# ETHERNET.net
KiCad netlist of a schematic drawn in Altium Designer
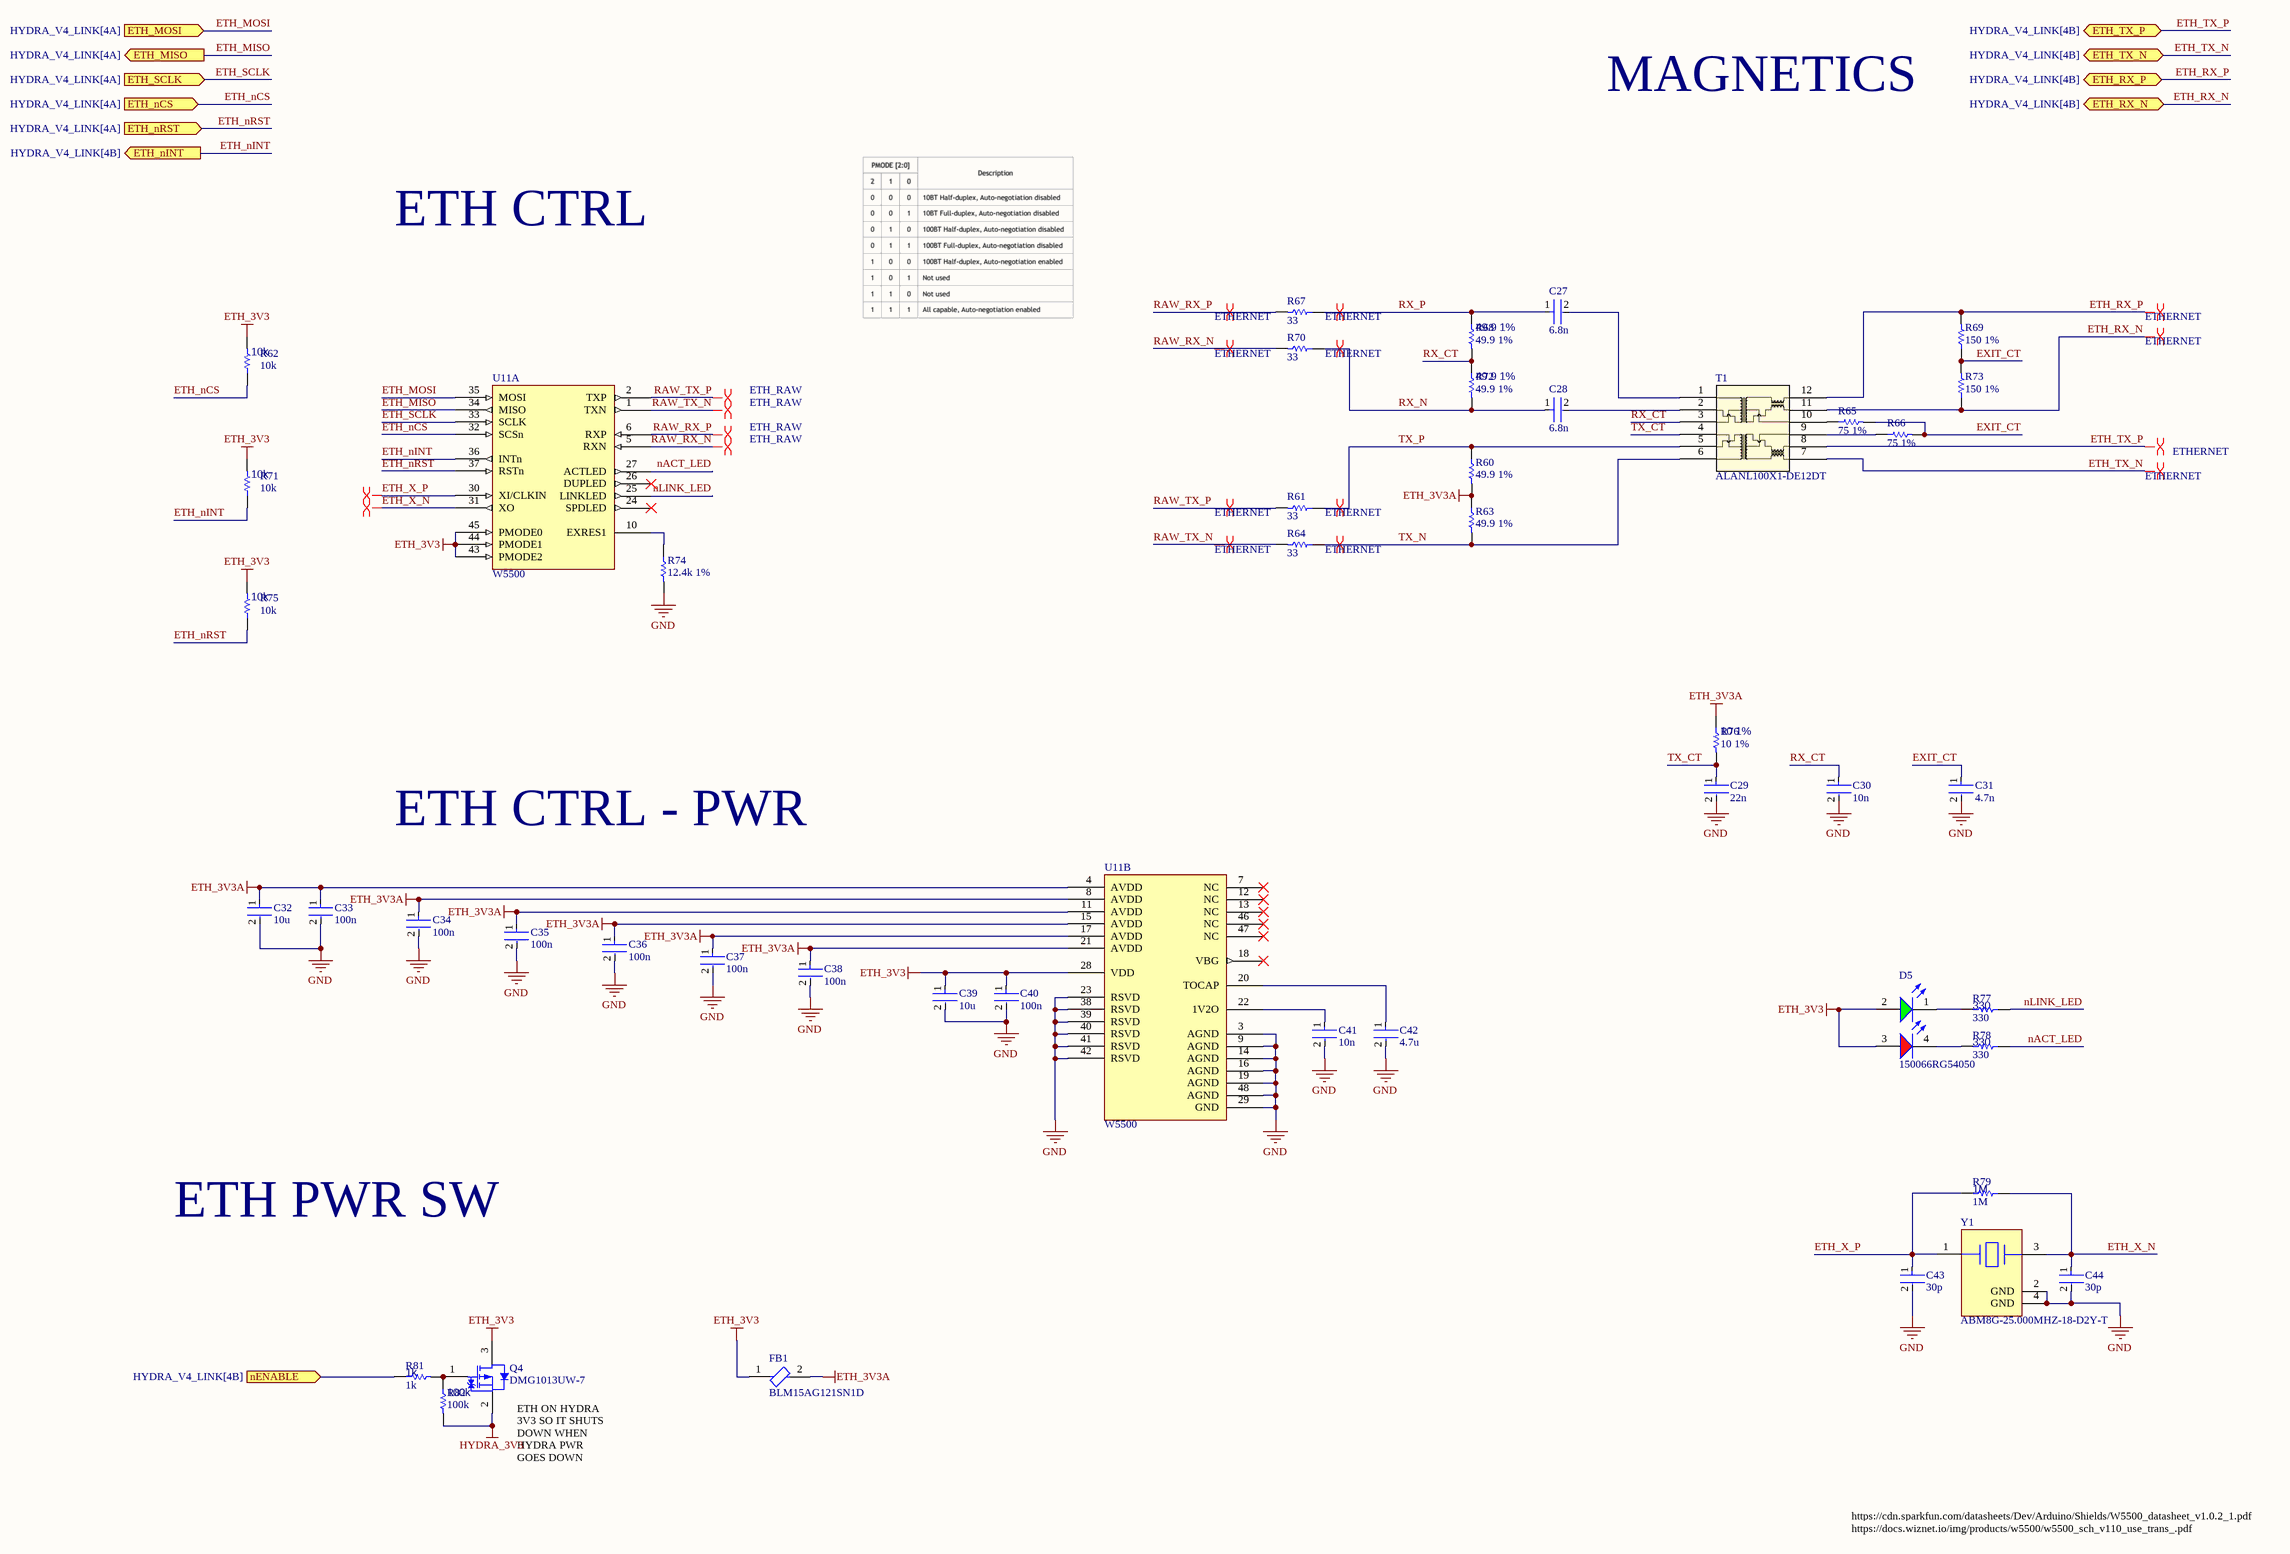
[diagram p0: ETHERNET.SchDoc]

(export (version "E")
  (design (tool "Eeschema 10.0.6"))
  (components
    (comp (ref "C27")
      (value "6.8n")
      (footprint "FP-0402-L_1_0_0_05-W_0_5-IPC_A")
      (description "LARGE PADS, 0402 CAP, CHANGE COMMENT TO MATCH REAL P/N")
      (libsource (lib "Space Concordia") (part "b4654b650e69147ec39a6b967a45e02"))
    )
    (comp (ref "C28")
      (value "6.8n")
      (footprint "FP-0402-L_1_0_0_05-W_0_5-IPC_A")
      (description "LARGE PADS, 0402 CAP, CHANGE COMMENT TO MATCH REAL P/N")
      (libsource (lib "Space Concordia") (part "b4654b650e69147ec39a6b967a45e02"))
    )
    (comp (ref "C29")
      (value "22n")
      (footprint "FP-0402-L_1_0_0_05-W_0_5-IPC_A")
      (description "LARGE PADS, 0402 CAP, CHANGE COMMENT TO MATCH REAL P/N")
      (libsource (lib "Space Concordia") (part "b4654b650e69147ec39a6b967a45e02"))
    )
    (comp (ref "C30")
      (value "10n")
      (footprint "FP-0402-L_1_0_0_05-W_0_5-IPC_A")
      (description "LARGE PADS, 0402 CAP, CHANGE COMMENT TO MATCH REAL P/N")
      (libsource (lib "Space Concordia") (part "b4654b650e69147ec39a6b967a45e02"))
    )
    (comp (ref "C31")
      (value "4.7n")
      (footprint "FP-0402-L_1_0_0_05-W_0_5-IPC_A")
      (description "LARGE PADS, 0402 CAP, CHANGE COMMENT TO MATCH REAL P/N")
      (libsource (lib "Space Concordia") (part "b4654b650e69147ec39a6b967a45e02"))
    )
    (comp (ref "C32")
      (value "10u")
      (footprint "FP-0402-L_1_0_0_05-W_0_5-IPC_A")
      (description "LARGE PADS, 0402 CAP, CHANGE COMMENT TO MATCH REAL P/N")
      (libsource (lib "Space Concordia") (part "b4654b650e69147ec39a6b967a45e02"))
    )
    (comp (ref "C33")
      (value "100n")
      (footprint "FP-0402-L_1_0_0_05-W_0_5-IPC_A")
      (description "LARGE PADS, 0402 CAP, CHANGE COMMENT TO MATCH REAL P/N")
      (libsource (lib "Space Concordia") (part "b4654b650e69147ec39a6b967a45e02"))
    )
    (comp (ref "C34")
      (value "100n")
      (footprint "FP-0402-L_1_0_0_05-W_0_5-IPC_A")
      (description "LARGE PADS, 0402 CAP, CHANGE COMMENT TO MATCH REAL P/N")
      (libsource (lib "Space Concordia") (part "b4654b650e69147ec39a6b967a45e02"))
    )
    (comp (ref "C35")
      (value "100n")
      (footprint "FP-0402-L_1_0_0_05-W_0_5-IPC_A")
      (description "LARGE PADS, 0402 CAP, CHANGE COMMENT TO MATCH REAL P/N")
      (libsource (lib "Space Concordia") (part "b4654b650e69147ec39a6b967a45e02"))
    )
    (comp (ref "C36")
      (value "100n")
      (footprint "FP-0402-L_1_0_0_05-W_0_5-IPC_A")
      (description "LARGE PADS, 0402 CAP, CHANGE COMMENT TO MATCH REAL P/N")
      (libsource (lib "Space Concordia") (part "b4654b650e69147ec39a6b967a45e02"))
    )
    (comp (ref "C37")
      (value "100n")
      (footprint "FP-0402-L_1_0_0_05-W_0_5-IPC_A")
      (description "LARGE PADS, 0402 CAP, CHANGE COMMENT TO MATCH REAL P/N")
      (libsource (lib "Space Concordia") (part "b4654b650e69147ec39a6b967a45e02"))
    )
    (comp (ref "C38")
      (value "100n")
      (footprint "FP-0402-L_1_0_0_05-W_0_5-IPC_A")
      (description "LARGE PADS, 0402 CAP, CHANGE COMMENT TO MATCH REAL P/N")
      (libsource (lib "Space Concordia") (part "b4654b650e69147ec39a6b967a45e02"))
    )
    (comp (ref "C39")
      (value "10u")
      (footprint "FP-0402-L_1_0_0_05-W_0_5-IPC_A")
      (description "LARGE PADS, 0402 CAP, CHANGE COMMENT TO MATCH REAL P/N")
      (libsource (lib "Space Concordia") (part "b4654b650e69147ec39a6b967a45e02"))
    )
    (comp (ref "C40")
      (value "100n")
      (footprint "FP-0402-L_1_0_0_05-W_0_5-IPC_A")
      (description "LARGE PADS, 0402 CAP, CHANGE COMMENT TO MATCH REAL P/N")
      (libsource (lib "Space Concordia") (part "b4654b650e69147ec39a6b967a45e02"))
    )
    (comp (ref "C41")
      (value "10n")
      (footprint "FP-0402-L_1_0_0_05-W_0_5-IPC_A")
      (description "LARGE PADS, 0402 CAP, CHANGE COMMENT TO MATCH REAL P/N")
      (libsource (lib "Space Concordia") (part "b4654b650e69147ec39a6b967a45e02"))
    )
    (comp (ref "C42")
      (value "4.7u")
      (footprint "FP-0402-L_1_0_0_05-W_0_5-IPC_A")
      (description "LARGE PADS, 0402 CAP, CHANGE COMMENT TO MATCH REAL P/N")
      (libsource (lib "Space Concordia") (part "b4654b650e69147ec39a6b967a45e02"))
    )
    (comp (ref "C43")
      (value "30p")
      (footprint "FP-0402-L_1_0_0_05-W_0_5-IPC_A")
      (description "LARGE PADS, 0402 CAP, CHANGE COMMENT TO MATCH REAL P/N")
      (libsource (lib "Space Concordia") (part "b4654b650e69147ec39a6b967a45e02"))
    )
    (comp (ref "C44")
      (value "30p")
      (footprint "FP-0402-L_1_0_0_05-W_0_5-IPC_A")
      (description "LARGE PADS, 0402 CAP, CHANGE COMMENT TO MATCH REAL P/N")
      (libsource (lib "Space Concordia") (part "b4654b650e69147ec39a6b967a45e02"))
    )
    (comp (ref "D5")
      (value "150066RG54050")
      (footprint "WL-SBCD_0606")
      (description "Led, Red/Grn, 180Mcd/230Mcd, 624Nm/525Nm Rohs Compliant: Yes")
      (fields (field (name "SOURCE") "rgled.SchLib"))
      (libsource (lib "Space Concordia") (part "CMP-004-00034-2"))
    )
    (comp (ref "FB1")
      (value "BLM15AG121SN1D")
      (footprint "FP-BLM15-0_05-MFG")
      (description "Chip Ferrite Bead, 0402, 120Ω @ 100MHz, 0.19Ω, 25%, 550mA")
      (fields (field (name "TOLERANCE") "25%"))
      (libsource (lib "Altium Content Vault") (part "5f30dd21d616792df468990f7003faa"))
    )
    (comp (ref "Q4")
      (value "DMG1013UW-7")
      (footprint "DIOD-SOT323-3_V")
      (fields (field (name "MANUFACTURER") "Diodes Inc"))
      (libsource (lib "Altium Content Vault") (part "PEMOS-GSD-3_C"))
    )
    (comp (ref "R60")
      (value "49.9 1%")
      (footprint "R0603B")
      (description "Resistor")
      (libsource (lib "Space Concordia") (part "Resistor"))
    )
    (comp (ref "R61")
      (value "33")
      (footprint "R0603B")
      (description "Resistor")
      (libsource (lib "Space Concordia") (part "Resistor"))
    )
    (comp (ref "R62")
      (value "10k")
      (footprint "R0603B")
      (description "Resistor")
      (fields (field (name "ALTIUM_VALUE") "10k"))
      (libsource (lib "Space Concordia") (part "Resistor"))
    )
    (comp (ref "R63")
      (value "49.9 1%")
      (footprint "R0603B")
      (description "Resistor")
      (libsource (lib "Space Concordia") (part "Resistor"))
    )
    (comp (ref "R64")
      (value "33")
      (footprint "R0603B")
      (description "Resistor")
      (libsource (lib "Space Concordia") (part "Resistor"))
    )
    (comp (ref "R65")
      (value "75 1%")
      (footprint "R0603B")
      (description "Resistor")
      (libsource (lib "Space Concordia") (part "Resistor"))
    )
    (comp (ref "R66")
      (value "75 1%")
      (footprint "R0603B")
      (description "Resistor")
      (libsource (lib "Space Concordia") (part "Resistor"))
    )
    (comp (ref "R67")
      (value "33")
      (footprint "R0603B")
      (description "Resistor")
      (libsource (lib "Space Concordia") (part "Resistor"))
    )
    (comp (ref "R68")
      (value "49.9 1%")
      (footprint "R0603B")
      (description "Resistor")
      (fields (field (name "ALTIUM_VALUE") "49.9 1%"))
      (libsource (lib "Space Concordia") (part "Resistor"))
    )
    (comp (ref "R69")
      (value "150 1%")
      (footprint "R0603B")
      (description "Resistor")
      (libsource (lib "Space Concordia") (part "Resistor"))
    )
    (comp (ref "R70")
      (value "33")
      (footprint "R0603B")
      (description "Resistor")
      (libsource (lib "Space Concordia") (part "Resistor"))
    )
    (comp (ref "R71")
      (value "10k")
      (footprint "R0603B")
      (description "Resistor")
      (fields (field (name "ALTIUM_VALUE") "10k"))
      (libsource (lib "Space Concordia") (part "Resistor"))
    )
    (comp (ref "R72")
      (value "49.9 1%")
      (footprint "R0603B")
      (description "Resistor")
      (fields (field (name "ALTIUM_VALUE") "49.9 1%"))
      (libsource (lib "Space Concordia") (part "Resistor"))
    )
    (comp (ref "R73")
      (value "150 1%")
      (footprint "R0603B")
      (description "Resistor")
      (libsource (lib "Space Concordia") (part "Resistor"))
    )
    (comp (ref "R74")
      (value "12.4k 1%")
      (footprint "R0603B")
      (description "Resistor")
      (libsource (lib "Space Concordia") (part "Resistor"))
    )
    (comp (ref "R75")
      (value "10k")
      (footprint "R0603B")
      (description "Resistor")
      (fields (field (name "ALTIUM_VALUE") "10k"))
      (libsource (lib "Space Concordia") (part "Resistor"))
    )
    (comp (ref "R76")
      (value "10 1%")
      (footprint "R0603B")
      (description "Resistor")
      (fields (field (name "ALTIUM_VALUE") "10 1%"))
      (libsource (lib "Space Concordia") (part "Resistor"))
    )
    (comp (ref "R77")
      (value "330")
      (footprint "R0603B")
      (description "Resistor")
      (fields (field (name "ALTIUM_VALUE") "330"))
      (libsource (lib "Space Concordia") (part "Resistor"))
    )
    (comp (ref "R78")
      (value "330")
      (footprint "R0603B")
      (description "Resistor")
      (fields (field (name "ALTIUM_VALUE") "330"))
      (libsource (lib "Space Concordia") (part "Resistor"))
    )
    (comp (ref "R79")
      (value "1M")
      (footprint "R0603B")
      (description "Resistor")
      (fields (field (name "ALTIUM_VALUE") "1M"))
      (libsource (lib "Space Concordia") (part "Resistor"))
    )
    (comp (ref "R81")
      (value "1k")
      (footprint "R0603B")
      (description "Resistor")
      (fields (field (name "ALTIUM_VALUE") "1k"))
      (libsource (lib "Space Concordia") (part "Resistor"))
    )
    (comp (ref "R82")
      (value "100k")
      (footprint "R0603B")
      (description "Resistor")
      (fields (field (name "ALTIUM_VALUE") "100k"))
      (libsource (lib "Space Concordia") (part "Resistor"))
    )
    (comp (ref "T1")
      (value "ALANL100X1-DE12DT")
      (footprint "ALANL100X1-DE12DT-Footprint-1")
      (description "Datacom Transformer, LAN; 10/100 BASE-TX; ETHERNET Application(s), 1CT:1CT")
      (libsource (lib "Space Concordia") (part "ALANL100X1-DE12DT"))
    )
    (comp (ref "U11")
      (value "W5500")
      (footprint "TSQFP50P900X900X160-48N")
      (description "Ethernet CTLR Single Chip 10Mbps/100Mbps 3.3V 48-Pin LQFP Reel")
      (libsource (lib "Space Concordia") (part "W5500"))
    )
    (comp (ref "Y1")
      (value "ABM8G-25.000MHZ-18-D2Y-T")
      (footprint "FP-ABM8G-MFG")
      (description "Crystal 25MHz ±20ppm (Tol) ±30ppm (Stability) 18pF FUND 60Ω 4-Pin SMD T/R")
      (fields (field (name "TOLERANCE") "20ppm"))
      (libsource (lib "Altium Content Vault") (part "48e526d86b7f2615d98721063c72f49"))
    )
  )
  (nets
    (net (code "1") (name "/ETH_MISO") (class "Default")
      (node (ref "U11") (pin "34") (pinfunction "MISO_34") (pintype "output"))
    )
    (net (code "2") (name "/ETH_MOSI") (class "Default")
      (node (ref "U11") (pin "35") (pinfunction "MOSI_35") (pintype "input"))
    )
    (net (code "3") (name "/ETH_RX_N") (class "Default")
      (node (ref "R73") (pin "1") (pinfunction "1_1") (pintype "passive"))
      (node (ref "T1") (pin "11") (pinfunction "MX1-_11") (pintype "passive"))
    )
    (net (code "4") (name "/ETH_RX_P") (class "Default")
      (node (ref "R69") (pin "2") (pinfunction "2_2") (pintype "passive"))
      (node (ref "T1") (pin "12") (pinfunction "MX1+_12") (pintype "passive"))
    )
    (net (code "5") (name "/ETH_SCLK") (class "Default")
      (node (ref "U11") (pin "33") (pinfunction "SCLK_33") (pintype "input"))
    )
    (net (code "6") (name "/ETH_TX_N") (class "Default")
      (node (ref "T1") (pin "7") (pinfunction "MX2-_7") (pintype "passive"))
    )
    (net (code "7") (name "/ETH_TX_P") (class "Default")
      (node (ref "T1") (pin "8") (pinfunction "MX2+_8") (pintype "passive"))
    )
    (net (code "8") (name "/ETH_X_N") (class "Default")
      (node (ref "C44") (pin "1") (pinfunction "1_1") (pintype "passive"))
      (node (ref "R79") (pin "1") (pinfunction "1_1") (pintype "passive"))
      (node (ref "U11") (pin "31") (pinfunction "XO_31") (pintype "output"))
      (node (ref "Y1") (pin "3") (pinfunction "3_3") (pintype "passive"))
    )
    (net (code "9") (name "/ETH_X_P") (class "Default")
      (node (ref "C43") (pin "1") (pinfunction "1_1") (pintype "passive"))
      (node (ref "R79") (pin "2") (pinfunction "2_2") (pintype "passive"))
      (node (ref "U11") (pin "30") (pinfunction "XI/CLKIN_30") (pintype "input"))
      (node (ref "Y1") (pin "1") (pinfunction "1_1") (pintype "passive"))
    )
    (net (code "10") (name "/ETH_nCS") (class "Default")
      (node (ref "R62") (pin "1") (pinfunction "1_1") (pintype "passive"))
      (node (ref "U11") (pin "32") (pinfunction "SCSn_32") (pintype "input"))
    )
    (net (code "11") (name "/ETH_nINT") (class "Default")
      (node (ref "R71") (pin "1") (pinfunction "1_1") (pintype "passive"))
      (node (ref "U11") (pin "36") (pinfunction "INTn_36") (pintype "output"))
    )
    (net (code "12") (name "/ETH_nRST") (class "Default")
      (node (ref "R75") (pin "1") (pinfunction "1_1") (pintype "passive"))
      (node (ref "U11") (pin "37") (pinfunction "RSTn_37") (pintype "input"))
    )
    (net (code "13") (name "/EXIT_CT") (class "Default")
      (node (ref "C31") (pin "1") (pinfunction "1_1") (pintype "passive"))
      (node (ref "R65") (pin "2") (pinfunction "2_2") (pintype "passive"))
      (node (ref "R66") (pin "2") (pinfunction "2_2") (pintype "passive"))
      (node (ref "R69") (pin "1") (pinfunction "1_1") (pintype "passive"))
      (node (ref "R73") (pin "2") (pinfunction "2_2") (pintype "passive"))
    )
    (net (code "14") (name "/RAW_RX_N") (class "Default")
      (node (ref "R70") (pin "2") (pinfunction "2_2") (pintype "passive"))
      (node (ref "U11") (pin "5") (pinfunction "RXN_5") (pintype "input"))
    )
    (net (code "15") (name "/RAW_RX_P") (class "Default")
      (node (ref "R67") (pin "2") (pinfunction "2_2") (pintype "passive"))
      (node (ref "U11") (pin "6") (pinfunction "RXP_6") (pintype "input"))
    )
    (net (code "16") (name "/RAW_TX_N") (class "Default")
      (node (ref "R64") (pin "2") (pinfunction "2_2") (pintype "passive"))
      (node (ref "U11") (pin "1") (pinfunction "TXN_1") (pintype "output"))
    )
    (net (code "17") (name "/RAW_TX_P") (class "Default")
      (node (ref "R61") (pin "2") (pinfunction "2_2") (pintype "passive"))
      (node (ref "U11") (pin "2") (pinfunction "TXP_2") (pintype "output"))
    )
    (net (code "18") (name "/RX_CT") (class "Default")
      (node (ref "C30") (pin "1") (pinfunction "1_1") (pintype "passive"))
      (node (ref "R68") (pin "2") (pinfunction "2_2") (pintype "passive"))
      (node (ref "R72") (pin "1") (pinfunction "1_1") (pintype "passive"))
      (node (ref "T1") (pin "3") (pinfunction "TCT1_3") (pintype "passive"))
    )
    (net (code "19") (name "/RX_N") (class "Default")
      (node (ref "C28") (pin "1") (pinfunction "1_1") (pintype "passive"))
      (node (ref "R70") (pin "1") (pinfunction "1_1") (pintype "passive"))
      (node (ref "R72") (pin "2") (pinfunction "2_2") (pintype "passive"))
    )
    (net (code "20") (name "/RX_P") (class "Default")
      (node (ref "C27") (pin "1") (pinfunction "1_1") (pintype "passive"))
      (node (ref "R67") (pin "1") (pinfunction "1_1") (pintype "passive"))
      (node (ref "R68") (pin "1") (pinfunction "1_1") (pintype "passive"))
    )
    (net (code "21") (name "/TX_CT") (class "Default")
      (node (ref "C29") (pin "1") (pinfunction "1_1") (pintype "passive"))
      (node (ref "R76") (pin "2") (pinfunction "2_2") (pintype "passive"))
      (node (ref "T1") (pin "4") (pinfunction "TCT2_4") (pintype "passive"))
    )
    (net (code "22") (name "/TX_N") (class "Default")
      (node (ref "R63") (pin "2") (pinfunction "2_2") (pintype "passive"))
      (node (ref "R64") (pin "1") (pinfunction "1_1") (pintype "passive"))
      (node (ref "T1") (pin "6") (pinfunction "TD2-_6") (pintype "passive"))
    )
    (net (code "23") (name "/TX_P") (class "Default")
      (node (ref "R60") (pin "1") (pinfunction "1_1") (pintype "passive"))
      (node (ref "R61") (pin "1") (pinfunction "1_1") (pintype "passive"))
      (node (ref "T1") (pin "5") (pinfunction "TD2+_5") (pintype "passive"))
    )
    (net (code "24") (name "/nACT_LED") (class "Default")
      (node (ref "R78") (pin "1") (pinfunction "1_1") (pintype "passive"))
      (node (ref "U11") (pin "27") (pinfunction "ACTLED_27") (pintype "output"))
    )
    (net (code "25") (name "/nENABLE") (class "Default")
      (node (ref "R81") (pin "1") (pinfunction "1_1") (pintype "passive"))
    )
    (net (code "26") (name "/nLINK_LED") (class "Default")
      (node (ref "R77") (pin "1") (pinfunction "1_1") (pintype "passive"))
      (node (ref "U11") (pin "25") (pinfunction "LINKLED_25") (pintype "output"))
    )
    (net (code "27") (name "ETH_3V3") (class "Default")
      (node (ref "C39") (pin "1") (pinfunction "1_1") (pintype "passive"))
      (node (ref "C40") (pin "1") (pinfunction "1_1") (pintype "passive"))
      (node (ref "D5") (pin "2") (pinfunction "A_2") (pintype "passive"))
      (node (ref "D5") (pin "3") (pinfunction "A_3") (pintype "passive"))
      (node (ref "FB1") (pin "1") (pinfunction "1_1") (pintype "passive"))
      (node (ref "Q4") (pin "3") (pinfunction "D_3") (pintype "passive"))
      (node (ref "R62") (pin "2") (pinfunction "2_2") (pintype "passive"))
      (node (ref "R71") (pin "2") (pinfunction "2_2") (pintype "passive"))
      (node (ref "R75") (pin "2") (pinfunction "2_2") (pintype "passive"))
      (node (ref "U11") (pin "28") (pinfunction "VDD_28") (pintype "power_in"))
      (node (ref "U11") (pin "43") (pinfunction "PMODE2_43") (pintype "input"))
      (node (ref "U11") (pin "44") (pinfunction "PMODE1_44") (pintype "input"))
      (node (ref "U11") (pin "45") (pinfunction "PMODE0_45") (pintype "input"))
    )
    (net (code "28") (name "ETH_3V3A") (class "Default")
      (node (ref "C32") (pin "1") (pinfunction "1_1") (pintype "passive"))
      (node (ref "C33") (pin "1") (pinfunction "1_1") (pintype "passive"))
      (node (ref "C34") (pin "1") (pinfunction "1_1") (pintype "passive"))
      (node (ref "C35") (pin "1") (pinfunction "1_1") (pintype "passive"))
      (node (ref "C36") (pin "1") (pinfunction "1_1") (pintype "passive"))
      (node (ref "C37") (pin "1") (pinfunction "1_1") (pintype "passive"))
      (node (ref "C38") (pin "1") (pinfunction "1_1") (pintype "passive"))
      (node (ref "FB1") (pin "2") (pinfunction "2_2") (pintype "passive"))
      (node (ref "R60") (pin "2") (pinfunction "2_2") (pintype "passive"))
      (node (ref "R63") (pin "1") (pinfunction "1_1") (pintype "passive"))
      (node (ref "R76") (pin "1") (pinfunction "1_1") (pintype "passive"))
      (node (ref "U11") (pin "11") (pinfunction "AVDD_11") (pintype "power_in"))
      (node (ref "U11") (pin "15") (pinfunction "AVDD_15") (pintype "power_in"))
      (node (ref "U11") (pin "17") (pinfunction "AVDD_17") (pintype "power_in"))
      (node (ref "U11") (pin "21") (pinfunction "AVDD_21") (pintype "power_in"))
      (node (ref "U11") (pin "4") (pinfunction "AVDD_4") (pintype "power_in"))
      (node (ref "U11") (pin "8") (pinfunction "AVDD_8") (pintype "power_in"))
    )
    (net (code "29") (name "GND") (class "Default")
      (node (ref "C29") (pin "2") (pinfunction "2_2") (pintype "passive"))
      (node (ref "C30") (pin "2") (pinfunction "2_2") (pintype "passive"))
      (node (ref "C31") (pin "2") (pinfunction "2_2") (pintype "passive"))
      (node (ref "C32") (pin "2") (pinfunction "2_2") (pintype "passive"))
      (node (ref "C33") (pin "2") (pinfunction "2_2") (pintype "passive"))
      (node (ref "C34") (pin "2") (pinfunction "2_2") (pintype "passive"))
      (node (ref "C35") (pin "2") (pinfunction "2_2") (pintype "passive"))
      (node (ref "C36") (pin "2") (pinfunction "2_2") (pintype "passive"))
      (node (ref "C37") (pin "2") (pinfunction "2_2") (pintype "passive"))
      (node (ref "C38") (pin "2") (pinfunction "2_2") (pintype "passive"))
      (node (ref "C39") (pin "2") (pinfunction "2_2") (pintype "passive"))
      (node (ref "C40") (pin "2") (pinfunction "2_2") (pintype "passive"))
      (node (ref "C41") (pin "2") (pinfunction "2_2") (pintype "passive"))
      (node (ref "C42") (pin "2") (pinfunction "2_2") (pintype "passive"))
      (node (ref "C43") (pin "2") (pinfunction "2_2") (pintype "passive"))
      (node (ref "C44") (pin "2") (pinfunction "2_2") (pintype "passive"))
      (node (ref "R74") (pin "2") (pinfunction "2_2") (pintype "passive"))
      (node (ref "U11") (pin "14") (pinfunction "AGND_14") (pintype "power_in"))
      (node (ref "U11") (pin "16") (pinfunction "AGND_16") (pintype "power_in"))
      (node (ref "U11") (pin "19") (pinfunction "AGND_19") (pintype "power_in"))
      (node (ref "U11") (pin "23") (pinfunction "RSVD_23") (pintype "passive"))
      (node (ref "U11") (pin "29") (pinfunction "GND_29") (pintype "power_in"))
      (node (ref "U11") (pin "3") (pinfunction "AGND_3") (pintype "power_in"))
      (node (ref "U11") (pin "38") (pinfunction "RSVD_38") (pintype "passive"))
      (node (ref "U11") (pin "39") (pinfunction "RSVD_39") (pintype "passive"))
      (node (ref "U11") (pin "40") (pinfunction "RSVD_40") (pintype "passive"))
      (node (ref "U11") (pin "41") (pinfunction "RSVD_41") (pintype "passive"))
      (node (ref "U11") (pin "42") (pinfunction "RSVD_42") (pintype "passive"))
      (node (ref "U11") (pin "48") (pinfunction "AGND_48") (pintype "power_in"))
      (node (ref "U11") (pin "9") (pinfunction "AGND_9") (pintype "power_in"))
      (node (ref "Y1") (pin "2") (pinfunction "GND_2") (pintype "power_in"))
      (node (ref "Y1") (pin "4") (pinfunction "GND_4") (pintype "power_in"))
    )
    (net (code "30") (name "HYDRA_3V3") (class "Default")
      (node (ref "Q4") (pin "2") (pinfunction "S_2") (pintype "passive"))
      (node (ref "R82") (pin "2") (pinfunction "2_2") (pintype "passive"))
    )
    (net (code "31") (name "Net-(D5-K-Pad1)") (class "Default")
      (node (ref "D5") (pin "1") (pinfunction "K_1") (pintype "passive"))
      (node (ref "R77") (pin "2") (pinfunction "2_2") (pintype "passive"))
    )
    (net (code "32") (name "Net-(D5-K-Pad4)") (class "Default")
      (node (ref "D5") (pin "4") (pinfunction "K_4") (pintype "passive"))
      (node (ref "R78") (pin "2") (pinfunction "2_2") (pintype "passive"))
    )
    (net (code "33") (name "Net-(Q4-G)") (class "Default")
      (node (ref "Q4") (pin "1") (pinfunction "G_1") (pintype "passive"))
      (node (ref "R81") (pin "2") (pinfunction "2_2") (pintype "passive"))
      (node (ref "R82") (pin "1") (pinfunction "1_1") (pintype "passive"))
    )
    (net (code "34") (name "Net-(T1-MCT1)") (class "Default")
      (node (ref "R65") (pin "1") (pinfunction "1_1") (pintype "passive"))
      (node (ref "T1") (pin "10") (pinfunction "MCT1_10") (pintype "passive"))
    )
    (net (code "35") (name "Net-(T1-MCT2)") (class "Default")
      (node (ref "R66") (pin "1") (pinfunction "1_1") (pintype "passive"))
      (node (ref "T1") (pin "9") (pinfunction "MCT2_9") (pintype "passive"))
    )
    (net (code "36") (name "Net-(T1-TD1+)") (class "Default")
      (node (ref "C27") (pin "2") (pinfunction "2_2") (pintype "passive"))
      (node (ref "T1") (pin "1") (pinfunction "TD1+_1") (pintype "passive"))
    )
    (net (code "37") (name "Net-(T1-TD1-)") (class "Default")
      (node (ref "C28") (pin "2") (pinfunction "2_2") (pintype "passive"))
      (node (ref "T1") (pin "2") (pinfunction "TD1-_2") (pintype "passive"))
    )
    (net (code "38") (name "Net-(U11A-EXRES1)") (class "Default")
      (node (ref "R74") (pin "1") (pinfunction "1_1") (pintype "passive"))
      (node (ref "U11") (pin "10") (pinfunction "EXRES1_10") (pintype "passive"))
    )
    (net (code "39") (name "Net-(U11B-1V2O)") (class "Default")
      (node (ref "C41") (pin "1") (pinfunction "1_1") (pintype "passive"))
      (node (ref "U11") (pin "22") (pinfunction "1V2O_22") (pintype "power_in"))
    )
    (net (code "40") (name "Net-(U11B-TOCAP)") (class "Default")
      (node (ref "C42") (pin "1") (pinfunction "1_1") (pintype "passive"))
      (node (ref "U11") (pin "20") (pinfunction "TOCAP_20") (pintype "passive"))
    )
    (net (code "41") (name "unconnected-(U11A-DUPLED-Pad26)") (class "Default")
      (node (ref "U11") (pin "26") (pinfunction "DUPLED_26") (pintype "output+no_connect"))
    )
    (net (code "42") (name "unconnected-(U11A-SPDLED-Pad24)") (class "Default")
      (node (ref "U11") (pin "24") (pinfunction "SPDLED_24") (pintype "output+no_connect"))
    )
    (net (code "43") (name "unconnected-(U11B-NC-Pad7)") (class "Default")
      (node (ref "U11") (pin "7") (pinfunction "NC_7") (pintype "passive+no_connect"))
    )
    (net (code "44") (name "unconnected-(U11B-NC-Pad12)") (class "Default")
      (node (ref "U11") (pin "12") (pinfunction "NC_12") (pintype "passive+no_connect"))
    )
    (net (code "45") (name "unconnected-(U11B-NC-Pad13)") (class "Default")
      (node (ref "U11") (pin "13") (pinfunction "NC_13") (pintype "passive+no_connect"))
    )
    (net (code "46") (name "unconnected-(U11B-NC-Pad46)") (class "Default")
      (node (ref "U11") (pin "46") (pinfunction "NC_46") (pintype "passive+no_connect"))
    )
    (net (code "47") (name "unconnected-(U11B-NC-Pad47)") (class "Default")
      (node (ref "U11") (pin "47") (pinfunction "NC_47") (pintype "passive+no_connect"))
    )
    (net (code "48") (name "unconnected-(U11B-VBG-Pad18)") (class "Default")
      (node (ref "U11") (pin "18") (pinfunction "VBG_18") (pintype "output+no_connect"))
    )
  )
)
